# Tut3.net
KiCad netlist of a schematic drawn in Altium Designer
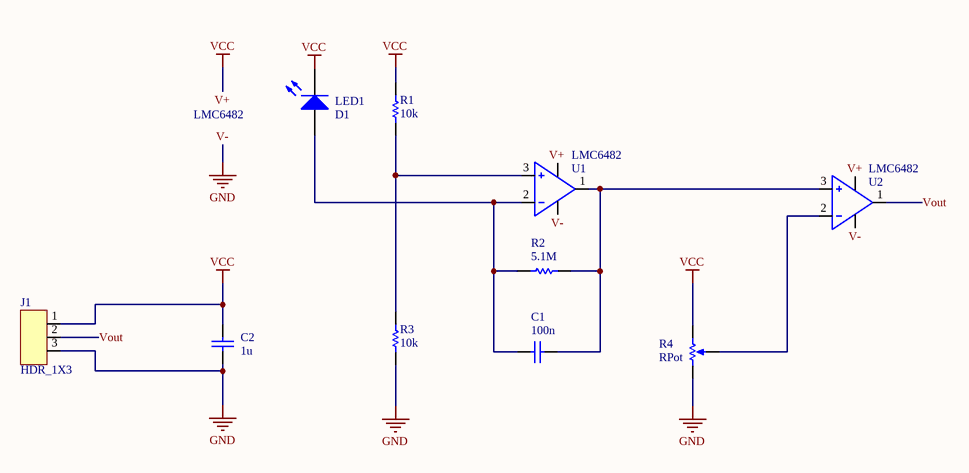
[diagram p0: Tut3.SchDoc]

(export (version "E")
  (design (tool "Eeschema 10.0.6"))
  (components
    (comp (ref "C1")
      (value "100n")
      (footprint "RAD-0.3")
      (description "Capacitor")
      (fields (field (name "PUBLISHER") "Altium Limited"))
      (libsource (lib "Miscellaneous Devices") (part "Cap"))
    )
    (comp (ref "C2")
      (value "1u")
      (footprint "RAD-0.3")
      (description "Capacitor")
      (fields (field (name "PUBLISHER") "Altium Limited"))
      (libsource (lib "Miscellaneous Devices") (part "Cap"))
    )
    (comp (ref "D1")
      (value "LED1")
      (footprint "LED-1")
      (description "Typical RED GaAs LED")
      (fields (field (name "PUBLISHER") "Altium Limited"))
      (libsource (lib "Miscellaneous Devices") (part "LED1"))
    )
    (comp (ref "J1")
      (value "HDR_1X3")
      (description "1X3 Header Connector")
      (libsource (lib "Tut3") (part "HDR_1X3"))
    )
    (comp (ref "R1")
      (value "10k")
      (footprint "AXIAL-0.3")
      (description "Resistor")
      (fields (field (name "PUBLISHER") "Altium Limited"))
      (libsource (lib "Miscellaneous Devices") (part "Res1"))
    )
    (comp (ref "R2")
      (value "5.1M")
      (footprint "AXIAL-0.3")
      (description "Resistor")
      (fields (field (name "PUBLISHER") "Altium Limited"))
      (libsource (lib "Miscellaneous Devices") (part "Res1"))
    )
    (comp (ref "R3")
      (value "10k")
      (footprint "AXIAL-0.3")
      (description "Resistor")
      (fields (field (name "PUBLISHER") "Altium Limited"))
      (libsource (lib "Miscellaneous Devices") (part "Res1"))
    )
    (comp (ref "R4")
      (value "RPot")
      (footprint "VR5")
      (description "Potentiometer")
      (fields (field (name "PUBLISHER") "Altium Limited"))
      (libsource (lib "Miscellaneous Devices") (part "RPot"))
    )
    (comp (ref "U1")
      (value "LMC6482")
      (description "CMOS Amplifier 2 Circuit Rail-to-Rail 8-SOIC")
      (libsource (lib "Tut3") (part "LMC6482"))
    )
    (comp (ref "U2")
      (value "LMC6482")
      (description "CMOS Amplifier 2 Circuit Rail-to-Rail 8-SOIC")
      (libsource (lib "Tut3") (part "LMC6482"))
    )
  )
  (nets
    (net (code "1") (name "/Vout") (class "Default")
      (node (ref "J1") (pin "2") (pintype "passive"))
      (node (ref "U2") (pin "1") (pinfunction "1_1") (pintype "passive"))
    )
    (net (code "2") (name "GND") (class "Default")
      (node (ref "C2") (pin "1") (pinfunction "1_1") (pintype "passive"))
      (node (ref "J1") (pin "3") (pintype "passive"))
      (node (ref "R3") (pin "1") (pinfunction "1_1") (pintype "passive"))
      (node (ref "R4") (pin "1") (pinfunction "TOP_1") (pintype "passive"))
      (node (ref "U1") (pin "5") (pinfunction "5_5") (pintype "passive"))
      (node (ref "U2") (pin "5") (pinfunction "5_5") (pintype "passive"))
    )
    (net (code "3") (name "Net-(C1-Pad2)") (class "Default")
      (node (ref "C1") (pin "2") (pinfunction "2_2") (pintype "passive"))
      (node (ref "R2") (pin "2") (pinfunction "2_2") (pintype "passive"))
      (node (ref "U1") (pin "1") (pinfunction "1_1") (pintype "passive"))
      (node (ref "U2") (pin "3") (pinfunction "3_3") (pintype "passive"))
    )
    (net (code "4") (name "Net-(D1-A)") (class "Default")
      (node (ref "C1") (pin "1") (pinfunction "1_1") (pintype "passive"))
      (node (ref "D1") (pin "1") (pinfunction "A_1") (pintype "passive"))
      (node (ref "R2") (pin "1") (pinfunction "1_1") (pintype "passive"))
      (node (ref "U1") (pin "2") (pinfunction "2_2") (pintype "passive"))
    )
    (net (code "5") (name "Net-(R1-Pad1)") (class "Default")
      (node (ref "R1") (pin "1") (pinfunction "1_1") (pintype "passive"))
      (node (ref "R3") (pin "2") (pinfunction "2_2") (pintype "passive"))
      (node (ref "U1") (pin "3") (pinfunction "3_3") (pintype "passive"))
    )
    (net (code "6") (name "Net-(R4-TAP)") (class "Default")
      (node (ref "R4") (pin "3") (pinfunction "TAP_3") (pintype "passive"))
      (node (ref "U2") (pin "2") (pinfunction "2_2") (pintype "passive"))
    )
    (net (code "7") (name "VCC") (class "Default")
      (node (ref "C2") (pin "2") (pinfunction "2_2") (pintype "passive"))
      (node (ref "D1") (pin "2") (pinfunction "K_2") (pintype "passive"))
      (node (ref "J1") (pin "1") (pintype "passive"))
      (node (ref "R1") (pin "2") (pinfunction "2_2") (pintype "passive"))
      (node (ref "R4") (pin "2") (pinfunction "BOT_2") (pintype "passive"))
      (node (ref "U1") (pin "4") (pinfunction "4_4") (pintype "passive"))
      (node (ref "U2") (pin "4") (pinfunction "4_4") (pintype "passive"))
    )
  )
)
